# GRBL-Control.net
KiCad netlist of a schematic drawn in EAGLE
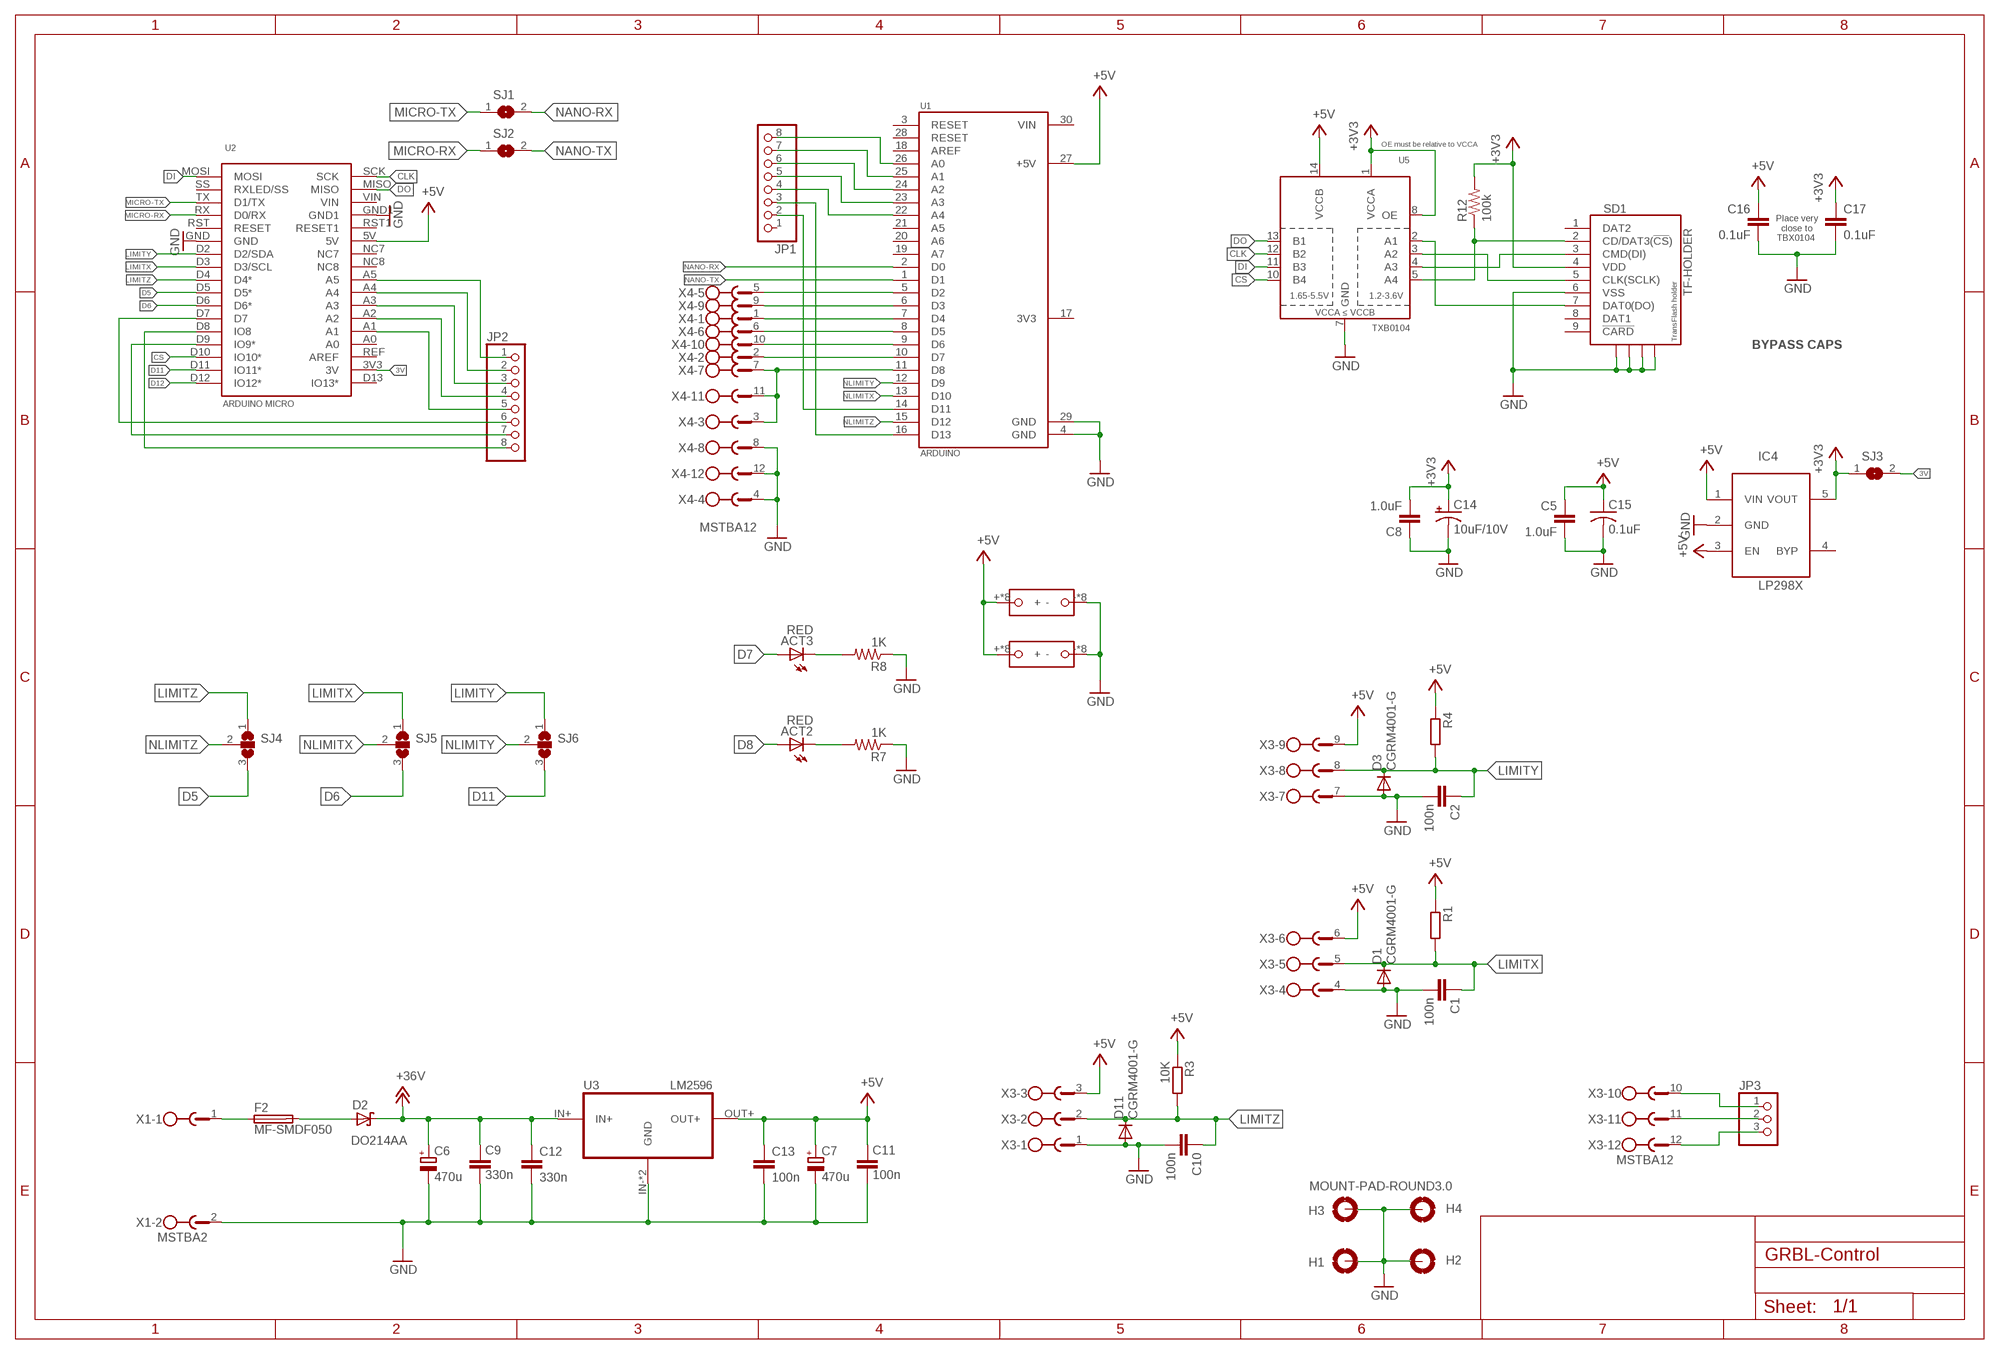
[diagram p0: schematic, sheet 1]

(export (version "E")
  (design (tool "Eeschema 10.0.6"))
  (components
    (comp (ref "ACT2")
      (value "RED")
      (footprint "eagle-import:CHIP-LED0805")
      (libsource (lib "eagle-import") (part "LEDCHIP-LED0805"))
    )
    (comp (ref "ACT3")
      (value "RED")
      (footprint "eagle-import:CHIP-LED0805")
      (libsource (lib "eagle-import") (part "LEDCHIP-LED0805"))
    )
    (comp (ref "C1")
      (value "100n")
      (footprint "eagle-import:C0603")
      (libsource (lib "eagle-import") (part "C-EUC0603"))
    )
    (comp (ref "C2")
      (value "100n")
      (footprint "eagle-import:C0603")
      (libsource (lib "eagle-import") (part "C-EUC0603"))
    )
    (comp (ref "C5")
      (value "1.0uF")
      (footprint "eagle-import:0603-CAP")
      (libsource (lib "eagle-import") (part "1.0UF-16V-10%(0603)"))
    )
    (comp (ref "C6")
      (value "470u")
      (footprint "eagle-import:E3,5-8")
      (libsource (lib "eagle-import") (part "CPOL-EUE3.5-8"))
    )
    (comp (ref "C7")
      (value "470u")
      (footprint "eagle-import:E3,5-8")
      (libsource (lib "eagle-import") (part "CPOL-EUE3.5-8"))
    )
    (comp (ref "C8")
      (value "1.0uF")
      (footprint "eagle-import:0603-CAP")
      (libsource (lib "eagle-import") (part "1.0UF-16V-10%(0603)"))
    )
    (comp (ref "C9")
      (value "330n")
      (footprint "eagle-import:C0603")
      (libsource (lib "eagle-import") (part "C-EUC0603"))
    )
    (comp (ref "C10")
      (value "100n")
      (footprint "eagle-import:C0603")
      (libsource (lib "eagle-import") (part "C-EUC0603"))
    )
    (comp (ref "C11")
      (value "100n")
      (footprint "eagle-import:C0603")
      (libsource (lib "eagle-import") (part "C-EUC0603"))
    )
    (comp (ref "C12")
      (value "330n")
      (footprint "eagle-import:C050-025X075")
      (libsource (lib "eagle-import") (part "RavinLib_C-EU050-025X075"))
    )
    (comp (ref "C13")
      (value "100n")
      (footprint "eagle-import:C050-025X075")
      (libsource (lib "eagle-import") (part "RavinLib_C-EU050-025X075"))
    )
    (comp (ref "C14")
      (value "10uF/10V")
      (footprint "eagle-import:A_3216-18R")
      (libsource (lib "eagle-import") (part "CPOL-USA/3216-18R"))
    )
    (comp (ref "C15")
      (value "0.1uF")
      (footprint "eagle-import:C0805K")
      (libsource (lib "eagle-import") (part "C-USC0805K"))
    )
    (comp (ref "C16")
      (value "0.1uF")
      (footprint "eagle-import:0603-CAP")
      (libsource (lib "eagle-import") (part "0.1UF-25V(+80/-20%)(0603)"))
    )
    (comp (ref "C17")
      (value "0.1uF")
      (footprint "eagle-import:0603-CAP")
      (libsource (lib "eagle-import") (part "0.1UF-25V(+80/-20%)(0603)"))
    )
    (comp (ref "D1")
      (value "CGRM4001-G")
      (footprint "eagle-import:SOD-123_MINI-SMA")
      (libsource (lib "eagle-import") (part "CGRM400-G1"))
    )
    (comp (ref "D2")
      (value "DO214AA")
      (footprint "eagle-import:SMB")
      (fields (field (name "PART-NO") "DO214AA"))
      (libsource (lib "eagle-import") (part "MBRS130LT3"))
    )
    (comp (ref "D3")
      (value "CGRM4001-G")
      (footprint "eagle-import:SOD-123_MINI-SMA")
      (libsource (lib "eagle-import") (part "CGRM400-G1"))
    )
    (comp (ref "D11")
      (value "CGRM4001-G")
      (footprint "eagle-import:SOD-123_MINI-SMA")
      (libsource (lib "eagle-import") (part "CGRM400-G1"))
    )
    (comp (ref "F2")
      (value "MF-SMDF050")
      (footprint "eagle-import:MF-SMDF050")
      (libsource (lib "eagle-import") (part "MF-SMDF050"))
    )
    (comp (ref "H1")
      (value "MOUNT-PAD-ROUND3.0")
      (footprint "eagle-import:3,0-PAD")
      (libsource (lib "eagle-import") (part "MOUNT-PAD-ROUND3.0"))
    )
    (comp (ref "H2")
      (value "MOUNT-PAD-ROUND3.0")
      (footprint "eagle-import:3,0-PAD")
      (libsource (lib "eagle-import") (part "MOUNT-PAD-ROUND3.0"))
    )
    (comp (ref "H3")
      (value "MOUNT-PAD-ROUND3.0")
      (footprint "eagle-import:3,0-PAD")
      (libsource (lib "eagle-import") (part "MOUNT-PAD-ROUND3.0"))
    )
    (comp (ref "H4")
      (value "MOUNT-PAD-ROUND3.0")
      (footprint "eagle-import:3,0-PAD")
      (libsource (lib "eagle-import") (part "MOUNT-PAD-ROUND3.0"))
    )
    (comp (ref "IC4")
      (value "LP298XS")
      (footprint "eagle-import:SOT23-5L")
      (libsource (lib "eagle-import") (part "LP298XS"))
    )
    (comp (ref "JP1")
      (value "PINHD-1X8BIG")
      (footprint "eagle-import:1X08-BIG")
      (libsource (lib "eagle-import") (part "PINHD-1X8BIG"))
    )
    (comp (ref "JP2")
      (value "PINHD-1X8BIG")
      (footprint "eagle-import:1X08-BIG")
      (libsource (lib "eagle-import") (part "PINHD-1X8BIG"))
    )
    (comp (ref "JP3")
      (value "PINHD-1X3")
      (footprint "eagle-import:1X03")
      (libsource (lib "eagle-import") (part "PINHD-1X3"))
    )
    (comp (ref "R1")
      (value "R-EU_R0603")
      (footprint "eagle-import:R0603")
      (libsource (lib "eagle-import") (part "R-EU_R0603"))
    )
    (comp (ref "R3")
      (value "10K")
      (footprint "eagle-import:R0603")
      (libsource (lib "eagle-import") (part "R-EU_R0603"))
    )
    (comp (ref "R4")
      (value "R-EU_R0603")
      (footprint "eagle-import:R0603")
      (libsource (lib "eagle-import") (part "R-EU_R0603"))
    )
    (comp (ref "R7")
      (value "1K")
      (footprint "eagle-import:R0805")
      (libsource (lib "eagle-import") (part "R-US_R0805"))
    )
    (comp (ref "R8")
      (value "1K")
      (footprint "eagle-import:R0805")
      (libsource (lib "eagle-import") (part "R-US_R0805"))
    )
    (comp (ref "R12")
      (value "100k")
      (footprint "eagle-import:0603-RES")
      (libsource (lib "eagle-import") (part "100KOHM-1/10W-1%(0603)"))
    )
    (comp (ref "SD1")
      (value "TF-HOLDER")
      (footprint "eagle-import:TF-PULL")
      (libsource (lib "eagle-import") (part "TF-HOLDER"))
    )
    (comp (ref "SJ1") (value "SJ") (footprint "eagle-import:SJ") (libsource (lib "eagle-import") (part "SJ")))
    (comp (ref "SJ2") (value "SJ") (footprint "eagle-import:SJ") (libsource (lib "eagle-import") (part "SJ")))
    (comp (ref "SJ3") (value "SJ") (footprint "eagle-import:SJ") (libsource (lib "eagle-import") (part "SJ")))
    (comp (ref "SJ4")
      (value "SJ2W")
      (footprint "eagle-import:SJ_2")
      (libsource (lib "eagle-import") (part "SJ2W"))
    )
    (comp (ref "SJ5")
      (value "SJ2W")
      (footprint "eagle-import:SJ_2")
      (libsource (lib "eagle-import") (part "SJ2W"))
    )
    (comp (ref "SJ6")
      (value "SJ2W")
      (footprint "eagle-import:SJ_2")
      (libsource (lib "eagle-import") (part "SJ2W"))
    )
    (comp (ref "U$1")
      (value "DEV_GRID")
      (footprint "eagle-import:DEV_GRID")
      (libsource (lib "eagle-import") (part "DEV_GRID"))
    )
    (comp (ref "U$2")
      (value "DEV_GRID")
      (footprint "eagle-import:DEV_GRID")
      (libsource (lib "eagle-import") (part "DEV_GRID"))
    )
    (comp (ref "U1")
      (value "ARDUINO")
      (footprint "eagle-import:ARDUINO_A000005")
      (libsource (lib "eagle-import") (part "ARDUINO"))
    )
    (comp (ref "U2")
      (value "ARDUINO MICRO")
      (footprint "eagle-import:ARDUINO-MICRO")
      (libsource (lib "eagle-import") (part "ARDUINO_MICROFOOTPRINT"))
    )
    (comp (ref "U3")
      (value "LM2596")
      (footprint "eagle-import:BUCK-LM2596")
      (libsource (lib "eagle-import") (part "LM2596-DCDC"))
    )
    (comp (ref "U5")
      (value "TXB0104")
      (footprint "eagle-import:SO14")
      (libsource (lib "eagle-import") (part "TXB0104PWRSOIC14"))
    )
    (comp (ref "X1")
      (value "MSTBA2")
      (footprint "eagle-import:MSTBA2")
      (fields (field (name "MF") "FARNELL") (field (name "MPN") "1757242"))
      (libsource (lib "eagle-import") (part "MSTBA2"))
    )
    (comp (ref "X3")
      (value "MSTBA12")
      (footprint "eagle-import:MSTBA12")
      (fields (field (name "MPN") "1757349"))
      (libsource (lib "eagle-import") (part "MSTBA12"))
    )
    (comp (ref "X4")
      (value "MSTBA12")
      (footprint "eagle-import:MSTBA12")
      (fields (field (name "MPN") "1757349"))
      (libsource (lib "eagle-import") (part "MSTBA12"))
    )
  )
  (nets
    (net (code "1") (name "+3V3") (class "Default")
      (node (ref "C14") (pin "+") (pinfunction "+_+") (pintype "passive"))
      (node (ref "C17") (pin "1") (pinfunction "1_1") (pintype "passive"))
      (node (ref "C8") (pin "2") (pinfunction "2_2") (pintype "passive"))
      (node (ref "IC4") (pin "5") (pinfunction "VOUT_5") (pintype "bidirectional"))
      (node (ref "R12") (pin "2") (pinfunction "2_2") (pintype "passive"))
      (node (ref "SD1") (pin "4") (pinfunction "VDD_4") (pintype "power_in"))
      (node (ref "SJ3") (pin "1") (pinfunction "1_1") (pintype "passive"))
      (node (ref "U5") (pin "1") (pinfunction "VCCA_1") (pintype "bidirectional"))
      (node (ref "U5") (pin "8") (pinfunction "OE_8") (pintype "bidirectional"))
    )
    (net (code "2") (name "+5V") (class "Default")
      (node (ref "C11") (pin "1") (pinfunction "1_1") (pintype "passive"))
      (node (ref "C13") (pin "1") (pinfunction "1_1") (pintype "passive"))
      (node (ref "C15") (pin "1") (pinfunction "1_1") (pintype "passive"))
      (node (ref "C16") (pin "1") (pinfunction "1_1") (pintype "passive"))
      (node (ref "C5") (pin "1") (pinfunction "1_1") (pintype "passive"))
      (node (ref "C7") (pin "+") (pinfunction "+_+") (pintype "passive"))
      (node (ref "IC4") (pin "1") (pinfunction "VIN_1") (pintype "bidirectional"))
      (node (ref "IC4") (pin "3") (pinfunction "EN_3") (pintype "bidirectional"))
      (node (ref "R1") (pin "1") (pinfunction "1_1") (pintype "passive"))
      (node (ref "R3") (pin "1") (pinfunction "1_1") (pintype "passive"))
      (node (ref "R4") (pin "1") (pinfunction "1_1") (pintype "passive"))
      (node (ref "U$1") (pin "+") (pinfunction "+_+") (pintype "bidirectional"))
      (node (ref "U$1") (pin "P$49") (pinfunction "+_P$49") (pintype "bidirectional"))
      (node (ref "U$1") (pin "P$50") (pinfunction "+_P$50") (pintype "bidirectional"))
      (node (ref "U$1") (pin "P$51") (pinfunction "+_P$51") (pintype "bidirectional"))
      (node (ref "U$1") (pin "P$52") (pinfunction "+_P$52") (pintype "bidirectional"))
      (node (ref "U$1") (pin "P$53") (pinfunction "+_P$53") (pintype "bidirectional"))
      (node (ref "U$1") (pin "P$54") (pinfunction "+_P$54") (pintype "bidirectional"))
      (node (ref "U$1") (pin "P$55") (pinfunction "+_P$55") (pintype "bidirectional"))
      (node (ref "U$2") (pin "+") (pinfunction "+_+") (pintype "bidirectional"))
      (node (ref "U$2") (pin "P$49") (pinfunction "+_P$49") (pintype "bidirectional"))
      (node (ref "U$2") (pin "P$50") (pinfunction "+_P$50") (pintype "bidirectional"))
      (node (ref "U$2") (pin "P$51") (pinfunction "+_P$51") (pintype "bidirectional"))
      (node (ref "U$2") (pin "P$52") (pinfunction "+_P$52") (pintype "bidirectional"))
      (node (ref "U$2") (pin "P$53") (pinfunction "+_P$53") (pintype "bidirectional"))
      (node (ref "U$2") (pin "P$54") (pinfunction "+_P$54") (pintype "bidirectional"))
      (node (ref "U$2") (pin "P$55") (pinfunction "+_P$55") (pintype "bidirectional"))
      (node (ref "U1") (pin "27") (pinfunction "+5V_27") (pintype "power_in"))
      (node (ref "U2") (pin "5V") (pinfunction "5V_5V") (pintype "bidirectional"))
      (node (ref "U3") (pin "OUT+") (pinfunction "OUT+_OUT+") (pintype "bidirectional"))
      (node (ref "U5") (pin "14") (pinfunction "VCCB_14") (pintype "bidirectional"))
      (node (ref "X3") (pin "3") (pinfunction "1_3") (pintype "passive"))
      (node (ref "X3") (pin "6") (pinfunction "1_6") (pintype "passive"))
      (node (ref "X3") (pin "9") (pinfunction "1_9") (pintype "passive"))
    )
    (net (code "3") (name "+36V") (class "Default")
      (node (ref "C12") (pin "1") (pinfunction "1_1") (pintype "passive"))
      (node (ref "C6") (pin "+") (pinfunction "+_+") (pintype "passive"))
      (node (ref "C9") (pin "1") (pinfunction "1_1") (pintype "passive"))
      (node (ref "D2") (pin "C") (pinfunction "C_C") (pintype "passive"))
      (node (ref "U3") (pin "IN+") (pinfunction "IN+_IN+") (pintype "bidirectional"))
    )
    (net (code "4") (name "/VIN") (class "Default")
      (node (ref "U1") (pin "30") (pinfunction "VIN_30") (pintype "power_in"))
    )
    (net (code "5") (name "3V") (class "Default")
      (node (ref "SJ3") (pin "2") (pinfunction "2_2") (pintype "passive"))
      (node (ref "U2") (pin "3V3") (pinfunction "3V_3V3") (pintype "bidirectional"))
    )
    (net (code "6") (name "CLK") (class "Default")
      (node (ref "U2") (pin "SCK") (pinfunction "SCK_SCK") (pintype "bidirectional"))
      (node (ref "U5") (pin "12") (pinfunction "B2_12") (pintype "bidirectional"))
    )
    (net (code "7") (name "CS") (class "Default")
      (node (ref "U2") (pin "D10") (pinfunction "IO10*_D10") (pintype "bidirectional"))
      (node (ref "U5") (pin "10") (pinfunction "B4_10") (pintype "bidirectional"))
    )
    (net (code "8") (name "D5") (class "Default")
      (node (ref "SJ4") (pin "3") (pinfunction "3_3") (pintype "passive"))
      (node (ref "U2") (pin "D5") (pinfunction "D5*_D5") (pintype "bidirectional"))
    )
    (net (code "9") (name "D6") (class "Default")
      (node (ref "SJ5") (pin "3") (pinfunction "3_3") (pintype "passive"))
      (node (ref "U2") (pin "D6") (pinfunction "D6*_D6") (pintype "bidirectional"))
    )
    (net (code "10") (name "D7") (class "Default")
      (node (ref "ACT3") (pin "A") (pinfunction "A_A") (pintype "passive"))
      (node (ref "JP2") (pin "6") (pinfunction "6_6") (pintype "passive"))
      (node (ref "U2") (pin "D7") (pinfunction "D7_D7") (pintype "bidirectional"))
    )
    (net (code "11") (name "D8") (class "Default")
      (node (ref "ACT2") (pin "A") (pinfunction "A_A") (pintype "passive"))
      (node (ref "JP2") (pin "8") (pinfunction "8_8") (pintype "passive"))
      (node (ref "U2") (pin "D8") (pinfunction "IO8_D8") (pintype "bidirectional"))
    )
    (net (code "12") (name "D11") (class "Default")
      (node (ref "SJ6") (pin "3") (pinfunction "3_3") (pintype "passive"))
      (node (ref "U2") (pin "D11") (pinfunction "IO11*_D11") (pintype "bidirectional"))
    )
    (net (code "13") (name "D12") (class "Default")
      (node (ref "U2") (pin "D12") (pinfunction "IO12*_D12") (pintype "bidirectional"))
    )
    (net (code "14") (name "DI") (class "Default")
      (node (ref "U2") (pin "MOSI") (pinfunction "MOSI_MOSI") (pintype "bidirectional"))
      (node (ref "U5") (pin "11") (pinfunction "B3_11") (pintype "bidirectional"))
    )
    (net (code "15") (name "DO") (class "Default")
      (node (ref "U2") (pin "MISO") (pinfunction "MISO_MISO") (pintype "bidirectional"))
      (node (ref "U5") (pin "13") (pinfunction "B1_13") (pintype "bidirectional"))
    )
    (net (code "16") (name "GND") (class "Default")
      (node (ref "C1") (pin "2") (pinfunction "2_2") (pintype "passive"))
      (node (ref "C10") (pin "2") (pinfunction "2_2") (pintype "passive"))
      (node (ref "C11") (pin "2") (pinfunction "2_2") (pintype "passive"))
      (node (ref "C12") (pin "2") (pinfunction "2_2") (pintype "passive"))
      (node (ref "C13") (pin "2") (pinfunction "2_2") (pintype "passive"))
      (node (ref "C14") (pin "-") (pinfunction "-_-") (pintype "passive"))
      (node (ref "C15") (pin "2") (pinfunction "2_2") (pintype "passive"))
      (node (ref "C16") (pin "2") (pinfunction "2_2") (pintype "passive"))
      (node (ref "C17") (pin "2") (pinfunction "2_2") (pintype "passive"))
      (node (ref "C2") (pin "2") (pinfunction "2_2") (pintype "passive"))
      (node (ref "C5") (pin "2") (pinfunction "2_2") (pintype "passive"))
      (node (ref "C6") (pin "-") (pinfunction "-_-") (pintype "passive"))
      (node (ref "C7") (pin "-") (pinfunction "-_-") (pintype "passive"))
      (node (ref "C8") (pin "1") (pinfunction "1_1") (pintype "passive"))
      (node (ref "C9") (pin "2") (pinfunction "2_2") (pintype "passive"))
      (node (ref "D1") (pin "A") (pinfunction "A_A") (pintype "passive"))
      (node (ref "D11") (pin "A") (pinfunction "A_A") (pintype "passive"))
      (node (ref "D3") (pin "A") (pinfunction "A_A") (pintype "passive"))
      (node (ref "H1") (pin "B3,0") (pinfunction "MOUNT_B3,0") (pintype "passive"))
      (node (ref "H1") (pin "P$1") (pinfunction "MOUNT_P$1") (pintype "passive"))
      (node (ref "H1") (pin "P$2") (pinfunction "MOUNT_P$2") (pintype "passive"))
      (node (ref "H1") (pin "P$3") (pinfunction "MOUNT_P$3") (pintype "passive"))
      (node (ref "H1") (pin "P$4") (pinfunction "MOUNT_P$4") (pintype "passive"))
      (node (ref "H1") (pin "P$5") (pinfunction "MOUNT_P$5") (pintype "passive"))
      (node (ref "H1") (pin "P$6") (pinfunction "MOUNT_P$6") (pintype "passive"))
      (node (ref "H1") (pin "P$7") (pinfunction "MOUNT_P$7") (pintype "passive"))
      (node (ref "H1") (pin "P$8") (pinfunction "MOUNT_P$8") (pintype "passive"))
      (node (ref "H2") (pin "B3,0") (pinfunction "MOUNT_B3,0") (pintype "passive"))
      (node (ref "H2") (pin "P$1") (pinfunction "MOUNT_P$1") (pintype "passive"))
      (node (ref "H2") (pin "P$2") (pinfunction "MOUNT_P$2") (pintype "passive"))
      (node (ref "H2") (pin "P$3") (pinfunction "MOUNT_P$3") (pintype "passive"))
      (node (ref "H2") (pin "P$4") (pinfunction "MOUNT_P$4") (pintype "passive"))
      (node (ref "H2") (pin "P$5") (pinfunction "MOUNT_P$5") (pintype "passive"))
      (node (ref "H2") (pin "P$6") (pinfunction "MOUNT_P$6") (pintype "passive"))
      (node (ref "H2") (pin "P$7") (pinfunction "MOUNT_P$7") (pintype "passive"))
      (node (ref "H2") (pin "P$8") (pinfunction "MOUNT_P$8") (pintype "passive"))
      (node (ref "H3") (pin "B3,0") (pinfunction "MOUNT_B3,0") (pintype "passive"))
      (node (ref "H3") (pin "P$1") (pinfunction "MOUNT_P$1") (pintype "passive"))
      (node (ref "H3") (pin "P$2") (pinfunction "MOUNT_P$2") (pintype "passive"))
      (node (ref "H3") (pin "P$3") (pinfunction "MOUNT_P$3") (pintype "passive"))
      (node (ref "H3") (pin "P$4") (pinfunction "MOUNT_P$4") (pintype "passive"))
      (node (ref "H3") (pin "P$5") (pinfunction "MOUNT_P$5") (pintype "passive"))
      (node (ref "H3") (pin "P$6") (pinfunction "MOUNT_P$6") (pintype "passive"))
      (node (ref "H3") (pin "P$7") (pinfunction "MOUNT_P$7") (pintype "passive"))
      (node (ref "H3") (pin "P$8") (pinfunction "MOUNT_P$8") (pintype "passive"))
      (node (ref "H4") (pin "B3,0") (pinfunction "MOUNT_B3,0") (pintype "passive"))
      (node (ref "H4") (pin "P$1") (pinfunction "MOUNT_P$1") (pintype "passive"))
      (node (ref "H4") (pin "P$2") (pinfunction "MOUNT_P$2") (pintype "passive"))
      (node (ref "H4") (pin "P$3") (pinfunction "MOUNT_P$3") (pintype "passive"))
      (node (ref "H4") (pin "P$4") (pinfunction "MOUNT_P$4") (pintype "passive"))
      (node (ref "H4") (pin "P$5") (pinfunction "MOUNT_P$5") (pintype "passive"))
      (node (ref "H4") (pin "P$6") (pinfunction "MOUNT_P$6") (pintype "passive"))
      (node (ref "H4") (pin "P$7") (pinfunction "MOUNT_P$7") (pintype "passive"))
      (node (ref "H4") (pin "P$8") (pinfunction "MOUNT_P$8") (pintype "passive"))
      (node (ref "IC4") (pin "2") (pinfunction "GND_2") (pintype "bidirectional"))
      (node (ref "R7") (pin "1") (pinfunction "1_1") (pintype "passive"))
      (node (ref "R8") (pin "1") (pinfunction "1_1") (pintype "passive"))
      (node (ref "SD1") (pin "6") (pinfunction "VSS_6") (pintype "power_in"))
      (node (ref "SD1") (pin "S1") (pinfunction "S1_S1") (pintype "passive"))
      (node (ref "SD1") (pin "S2") (pinfunction "S2_S2") (pintype "passive"))
      (node (ref "SD1") (pin "S3") (pinfunction "S3_S3") (pintype "passive"))
      (node (ref "SD1") (pin "S4") (pinfunction "S4_S4") (pintype "passive"))
      (node (ref "U$1") (pin "-") (pinfunction "-_-") (pintype "bidirectional"))
      (node (ref "U$1") (pin "P$57") (pinfunction "-_P$57") (pintype "bidirectional"))
      (node (ref "U$1") (pin "P$58") (pinfunction "-_P$58") (pintype "bidirectional"))
      (node (ref "U$1") (pin "P$59") (pinfunction "-_P$59") (pintype "bidirectional"))
      (node (ref "U$1") (pin "P$60") (pinfunction "-_P$60") (pintype "bidirectional"))
      (node (ref "U$1") (pin "P$61") (pinfunction "-_P$61") (pintype "bidirectional"))
      (node (ref "U$1") (pin "P$62") (pinfunction "-_P$62") (pintype "bidirectional"))
      (node (ref "U$1") (pin "P$63") (pinfunction "-_P$63") (pintype "bidirectional"))
      (node (ref "U$2") (pin "-") (pinfunction "-_-") (pintype "bidirectional"))
      (node (ref "U$2") (pin "P$57") (pinfunction "-_P$57") (pintype "bidirectional"))
      (node (ref "U$2") (pin "P$58") (pinfunction "-_P$58") (pintype "bidirectional"))
      (node (ref "U$2") (pin "P$59") (pinfunction "-_P$59") (pintype "bidirectional"))
      (node (ref "U$2") (pin "P$60") (pinfunction "-_P$60") (pintype "bidirectional"))
      (node (ref "U$2") (pin "P$61") (pinfunction "-_P$61") (pintype "bidirectional"))
      (node (ref "U$2") (pin "P$62") (pinfunction "-_P$62") (pintype "bidirectional"))
      (node (ref "U$2") (pin "P$63") (pinfunction "-_P$63") (pintype "bidirectional"))
      (node (ref "U1") (pin "29") (pinfunction "GND_29") (pintype "power_in"))
      (node (ref "U1") (pin "4") (pinfunction "GND_4") (pintype "power_in"))
      (node (ref "U2") (pin "GND") (pinfunction "GND_GND") (pintype "bidirectional"))
      (node (ref "U2") (pin "GND1") (pinfunction "GND1_GND1") (pintype "bidirectional"))
      (node (ref "U3") (pin "IN-") (pinfunction "GND_IN-") (pintype "bidirectional"))
      (node (ref "U3") (pin "OUT-") (pinfunction "GND_OUT-") (pintype "bidirectional"))
      (node (ref "U5") (pin "7") (pinfunction "GND_7") (pintype "bidirectional"))
      (node (ref "X1") (pin "2") (pinfunction "1_2") (pintype "passive"))
      (node (ref "X3") (pin "1") (pinfunction "1_1") (pintype "passive"))
      (node (ref "X3") (pin "4") (pinfunction "1_4") (pintype "passive"))
      (node (ref "X3") (pin "7") (pinfunction "1_7") (pintype "passive"))
      (node (ref "X4") (pin "12") (pinfunction "1_12") (pintype "passive"))
      (node (ref "X4") (pin "4") (pinfunction "1_4") (pintype "passive"))
      (node (ref "X4") (pin "8") (pinfunction "1_8") (pintype "passive"))
    )
    (net (code "17") (name "LIMITX") (class "Default")
      (node (ref "C1") (pin "1") (pinfunction "1_1") (pintype "passive"))
      (node (ref "D1") (pin "C") (pinfunction "C_C") (pintype "passive"))
      (node (ref "R1") (pin "2") (pinfunction "2_2") (pintype "passive"))
      (node (ref "SJ5") (pin "1") (pinfunction "1_1") (pintype "passive"))
      (node (ref "U2") (pin "D3") (pinfunction "D3/SCL_D3") (pintype "bidirectional"))
      (node (ref "X3") (pin "5") (pinfunction "1_5") (pintype "passive"))
    )
    (net (code "18") (name "LIMITY") (class "Default")
      (node (ref "C2") (pin "1") (pinfunction "1_1") (pintype "passive"))
      (node (ref "D3") (pin "C") (pinfunction "C_C") (pintype "passive"))
      (node (ref "R4") (pin "2") (pinfunction "2_2") (pintype "passive"))
      (node (ref "SJ6") (pin "1") (pinfunction "1_1") (pintype "passive"))
      (node (ref "U2") (pin "D2") (pinfunction "D2/SDA_D2") (pintype "bidirectional"))
      (node (ref "X3") (pin "8") (pinfunction "1_8") (pintype "passive"))
    )
    (net (code "19") (name "LIMITZ") (class "Default")
      (node (ref "C10") (pin "1") (pinfunction "1_1") (pintype "passive"))
      (node (ref "D11") (pin "C") (pinfunction "C_C") (pintype "passive"))
      (node (ref "R3") (pin "2") (pinfunction "2_2") (pintype "passive"))
      (node (ref "SJ4") (pin "1") (pinfunction "1_1") (pintype "passive"))
      (node (ref "U2") (pin "D4") (pinfunction "D4*_D4") (pintype "bidirectional"))
      (node (ref "X3") (pin "2") (pinfunction "1_2") (pintype "passive"))
    )
    (net (code "20") (name "MICRO-RX") (class "Default")
      (node (ref "SJ2") (pin "1") (pinfunction "1_1") (pintype "passive"))
      (node (ref "U2") (pin "RX") (pinfunction "D0/RX_RX") (pintype "bidirectional"))
    )
    (net (code "21") (name "MICRO-TX") (class "Default")
      (node (ref "SJ1") (pin "1") (pinfunction "1_1") (pintype "passive"))
      (node (ref "U2") (pin "TX") (pinfunction "D1/TX_TX") (pintype "bidirectional"))
    )
    (net (code "22") (name "NANO-RX") (class "Default")
      (node (ref "SJ1") (pin "2") (pinfunction "2_2") (pintype "passive"))
      (node (ref "U1") (pin "2") (pinfunction "D0_2") (pintype "bidirectional"))
    )
    (net (code "23") (name "NANO-TX") (class "Default")
      (node (ref "SJ2") (pin "2") (pinfunction "2_2") (pintype "passive"))
      (node (ref "U1") (pin "1") (pinfunction "D1_1") (pintype "bidirectional"))
    )
    (net (code "24") (name "NLIMITX") (class "Default")
      (node (ref "SJ5") (pin "2") (pinfunction "2_2") (pintype "passive"))
      (node (ref "U1") (pin "13") (pinfunction "D10_13") (pintype "bidirectional"))
    )
    (net (code "25") (name "NLIMITY") (class "Default")
      (node (ref "SJ6") (pin "2") (pinfunction "2_2") (pintype "passive"))
      (node (ref "U1") (pin "12") (pinfunction "D9_12") (pintype "bidirectional"))
    )
    (net (code "26") (name "NLIMITZ") (class "Default")
      (node (ref "SJ4") (pin "2") (pinfunction "2_2") (pintype "passive"))
      (node (ref "U1") (pin "15") (pinfunction "D12_15") (pintype "bidirectional"))
    )
    (net (code "27") (name "Net-(ACT2-PadC)") (class "Default")
      (node (ref "ACT2") (pin "C") (pinfunction "C_C") (pintype "passive"))
      (node (ref "R7") (pin "2") (pinfunction "2_2") (pintype "passive"))
    )
    (net (code "28") (name "Net-(ACT3-PadC)") (class "Default")
      (node (ref "ACT3") (pin "C") (pinfunction "C_C") (pintype "passive"))
      (node (ref "R8") (pin "2") (pinfunction "2_2") (pintype "passive"))
    )
    (net (code "29") (name "Net-(D2-PadA)") (class "Default")
      (node (ref "D2") (pin "A") (pinfunction "A_A") (pintype "passive"))
      (node (ref "F2") (pin "2") (pinfunction "2_2") (pintype "passive"))
    )
    (net (code "30") (name "Net-(F2-Pad1)") (class "Default")
      (node (ref "F2") (pin "1") (pinfunction "1_1") (pintype "passive"))
      (node (ref "X1") (pin "1") (pinfunction "1_1") (pintype "passive"))
    )
    (net (code "31") (name "Net-(JP2-Pad1)") (class "Default")
      (node (ref "JP2") (pin "1") (pinfunction "1_1") (pintype "passive"))
      (node (ref "U2") (pin "A5") (pinfunction "A5_A5") (pintype "bidirectional"))
    )
    (net (code "32") (name "Net-(JP2-Pad2)") (class "Default")
      (node (ref "JP2") (pin "2") (pinfunction "2_2") (pintype "passive"))
      (node (ref "U2") (pin "A4") (pinfunction "A4_A4") (pintype "bidirectional"))
    )
    (net (code "33") (name "Net-(JP2-Pad3)") (class "Default")
      (node (ref "JP2") (pin "3") (pinfunction "3_3") (pintype "passive"))
      (node (ref "U2") (pin "A3") (pinfunction "A3_A3") (pintype "bidirectional"))
    )
    (net (code "34") (name "Net-(JP2-Pad4)") (class "Default")
      (node (ref "JP2") (pin "4") (pinfunction "4_4") (pintype "passive"))
      (node (ref "U2") (pin "A2") (pinfunction "A2_A2") (pintype "bidirectional"))
    )
    (net (code "35") (name "Net-(JP2-Pad5)") (class "Default")
      (node (ref "JP2") (pin "5") (pinfunction "5_5") (pintype "passive"))
      (node (ref "U2") (pin "A1") (pinfunction "A1_A1") (pintype "bidirectional"))
    )
    (net (code "36") (name "Net-(SD1-CD{slash}DAT3(~{CS}))") (class "Default")
      (node (ref "R12") (pin "1") (pinfunction "1_1") (pintype "passive"))
      (node (ref "SD1") (pin "2") (pinfunction "CD/DAT3(~{CS})_2") (pintype "bidirectional"))
      (node (ref "U5") (pin "5") (pinfunction "A4_5") (pintype "bidirectional"))
    )
    (net (code "37") (name "Net-(SD1-CLK(SCLK))") (class "Default")
      (node (ref "SD1") (pin "5") (pinfunction "CLK(SCLK)_5") (pintype "input"))
      (node (ref "U5") (pin "3") (pinfunction "A2_3") (pintype "bidirectional"))
    )
    (net (code "38") (name "Net-(SD1-CMD(DI))") (class "Default")
      (node (ref "SD1") (pin "3") (pinfunction "CMD(DI)_3") (pintype "bidirectional"))
      (node (ref "U5") (pin "4") (pinfunction "A3_4") (pintype "bidirectional"))
    )
    (net (code "39") (name "Net-(SD1-DAT0(DO))") (class "Default")
      (node (ref "SD1") (pin "7") (pinfunction "DAT0(DO)_7") (pintype "bidirectional"))
      (node (ref "U5") (pin "2") (pinfunction "A1_2") (pintype "bidirectional"))
    )
    (net (code "40") (name "Net-(U1-A0)") (class "Default")
      (node (ref "JP1") (pin "8") (pinfunction "8_8") (pintype "passive"))
      (node (ref "U1") (pin "26") (pinfunction "A0_26") (pintype "input"))
    )
    (net (code "41") (name "Net-(U1-A1)") (class "Default")
      (node (ref "JP1") (pin "7") (pinfunction "7_7") (pintype "passive"))
      (node (ref "U1") (pin "25") (pinfunction "A1_25") (pintype "input"))
    )
    (net (code "42") (name "Net-(U1-A2)") (class "Default")
      (node (ref "JP1") (pin "6") (pinfunction "6_6") (pintype "passive"))
      (node (ref "U1") (pin "24") (pinfunction "A2_24") (pintype "input"))
    )
    (net (code "43") (name "Net-(U1-A3)") (class "Default")
      (node (ref "JP1") (pin "5") (pinfunction "5_5") (pintype "passive"))
      (node (ref "U1") (pin "23") (pinfunction "A3_23") (pintype "input"))
    )
    (net (code "44") (name "Net-(U1-A4)") (class "Default")
      (node (ref "JP1") (pin "4") (pinfunction "4_4") (pintype "passive"))
      (node (ref "U1") (pin "22") (pinfunction "A4_22") (pintype "input"))
    )
    (net (code "45") (name "Net-(U1-D2)") (class "Default")
      (node (ref "U1") (pin "5") (pinfunction "D2_5") (pintype "bidirectional"))
      (node (ref "X4") (pin "5") (pinfunction "1_5") (pintype "passive"))
    )
    (net (code "46") (name "Net-(U1-D3)") (class "Default")
      (node (ref "U1") (pin "6") (pinfunction "D3_6") (pintype "bidirectional"))
      (node (ref "X4") (pin "9") (pinfunction "1_9") (pintype "passive"))
    )
    (net (code "47") (name "Net-(U1-D4)") (class "Default")
      (node (ref "U1") (pin "7") (pinfunction "D4_7") (pintype "bidirectional"))
      (node (ref "X4") (pin "1") (pinfunction "1_1") (pintype "passive"))
    )
    (net (code "48") (name "Net-(U1-D5)") (class "Default")
      (node (ref "U1") (pin "8") (pinfunction "D5_8") (pintype "bidirectional"))
      (node (ref "X4") (pin "6") (pinfunction "1_6") (pintype "passive"))
    )
    (net (code "49") (name "Net-(U1-D6)") (class "Default")
      (node (ref "U1") (pin "9") (pinfunction "D6_9") (pintype "bidirectional"))
      (node (ref "X4") (pin "10") (pinfunction "1_10") (pintype "passive"))
    )
    (net (code "50") (name "Net-(U1-D7)") (class "Default")
      (node (ref "U1") (pin "10") (pinfunction "D7_10") (pintype "bidirectional"))
      (node (ref "X4") (pin "2") (pinfunction "1_2") (pintype "passive"))
    )
    (net (code "51") (name "Net-(U1-D8)") (class "Default")
      (node (ref "U1") (pin "11") (pinfunction "D8_11") (pintype "bidirectional"))
      (node (ref "X4") (pin "11") (pinfunction "1_11") (pintype "passive"))
      (node (ref "X4") (pin "3") (pinfunction "1_3") (pintype "passive"))
      (node (ref "X4") (pin "7") (pinfunction "1_7") (pintype "passive"))
    )
    (net (code "52") (name "Net-(U1-D11)") (class "Default")
      (node (ref "JP1") (pin "2") (pinfunction "2_2") (pintype "passive"))
      (node (ref "U1") (pin "14") (pinfunction "D11_14") (pintype "bidirectional"))
    )
    (net (code "53") (name "Net-(U1-D13)") (class "Default")
      (node (ref "JP1") (pin "3") (pinfunction "3_3") (pintype "passive"))
      (node (ref "U1") (pin "16") (pinfunction "D13_16") (pintype "bidirectional"))
    )
    (net (code "54") (name "Net-(U2-IO9*)") (class "Default")
      (node (ref "JP2") (pin "7") (pinfunction "7_7") (pintype "passive"))
      (node (ref "U2") (pin "D9") (pinfunction "IO9*_D9") (pintype "bidirectional"))
    )
    (net (code "55") (name "Net-(X3B-1)") (class "Default")
      (node (ref "JP3") (pin "1") (pinfunction "1_1") (pintype "passive"))
      (node (ref "X3") (pin "10") (pinfunction "1_10") (pintype "passive"))
    )
    (net (code "56") (name "Net-(X3C-1)") (class "Default")
      (node (ref "JP3") (pin "2") (pinfunction "2_2") (pintype "passive"))
      (node (ref "X3") (pin "11") (pinfunction "1_11") (pintype "passive"))
    )
    (net (code "57") (name "Net-(X3D-1)") (class "Default")
      (node (ref "JP3") (pin "3") (pinfunction "3_3") (pintype "passive"))
      (node (ref "X3") (pin "12") (pinfunction "1_12") (pintype "passive"))
    )
    (net (code "58") (name "unconnected-(IC4-BYP-Pad4)") (class "Default")
      (node (ref "IC4") (pin "4") (pinfunction "BYP_4") (pintype "bidirectional"))
    )
    (net (code "59") (name "unconnected-(JP1-Pad1)") (class "Default")
      (node (ref "JP1") (pin "1") (pinfunction "1_1") (pintype "passive"))
    )
    (net (code "60") (name "unconnected-(SD1-DAT1-Pad8)") (class "Default")
      (node (ref "SD1") (pin "8") (pinfunction "DAT1_8") (pintype "bidirectional"))
    )
    (net (code "61") (name "unconnected-(SD1-DAT2-Pad1)") (class "Default")
      (node (ref "SD1") (pin "1") (pinfunction "DAT2_1") (pintype "bidirectional"))
    )
    (net (code "62") (name "unconnected-(SD1-~{CARD}-Pad9)") (class "Default")
      (node (ref "SD1") (pin "9") (pinfunction "~{CARD}_9") (pintype "passive"))
    )
    (net (code "63") (name "unconnected-(U1-3V3-Pad17)") (class "Default")
      (node (ref "U1") (pin "17") (pinfunction "3V3_17") (pintype "output"))
    )
    (net (code "64") (name "unconnected-(U1-A5-Pad21)") (class "Default")
      (node (ref "U1") (pin "21") (pinfunction "A5_21") (pintype "input"))
    )
    (net (code "65") (name "unconnected-(U1-A6-Pad20)") (class "Default")
      (node (ref "U1") (pin "20") (pinfunction "A6_20") (pintype "input"))
    )
    (net (code "66") (name "unconnected-(U1-A7-Pad19)") (class "Default")
      (node (ref "U1") (pin "19") (pinfunction "A7_19") (pintype "input"))
    )
    (net (code "67") (name "unconnected-(U1-AREF-Pad18)") (class "Default")
      (node (ref "U1") (pin "18") (pinfunction "AREF_18") (pintype "input"))
    )
    (net (code "68") (name "unconnected-(U1-RESET-Pad3)") (class "Default")
      (node (ref "U1") (pin "3") (pinfunction "RESET_3") (pintype "input"))
    )
    (net (code "69") (name "unconnected-(U1-RESET-Pad28)") (class "Default")
      (node (ref "U1") (pin "28") (pinfunction "RESET_28") (pintype "input"))
    )
    (net (code "70") (name "unconnected-(U2-AREF-PadREF)") (class "Default")
      (node (ref "U2") (pin "REF") (pinfunction "AREF_REF") (pintype "bidirectional"))
    )
    (net (code "71") (name "unconnected-(U2-IO13*-PadD13)") (class "Default")
      (node (ref "U2") (pin "D13") (pinfunction "IO13*_D13") (pintype "bidirectional"))
    )
    (net (code "72") (name "unconnected-(U2-PadA0)") (class "Default")
      (node (ref "U2") (pin "A0") (pinfunction "A0_A0") (pintype "bidirectional"))
    )
    (net (code "73") (name "unconnected-(U2-PadNC7)") (class "Default")
      (node (ref "U2") (pin "NC7") (pinfunction "NC7_NC7") (pintype "bidirectional"))
    )
    (net (code "74") (name "unconnected-(U2-PadNC8)") (class "Default")
      (node (ref "U2") (pin "NC8") (pinfunction "NC8_NC8") (pintype "bidirectional"))
    )
    (net (code "75") (name "unconnected-(U2-PadVIN)") (class "Default")
      (node (ref "U2") (pin "VIN") (pinfunction "VIN_VIN") (pintype "bidirectional"))
    )
    (net (code "76") (name "unconnected-(U2-RESET-PadRST)") (class "Default")
      (node (ref "U2") (pin "RST") (pinfunction "RESET_RST") (pintype "bidirectional"))
    )
    (net (code "77") (name "unconnected-(U2-RESET1-PadRST1)") (class "Default")
      (node (ref "U2") (pin "RST1") (pinfunction "RESET1_RST1") (pintype "bidirectional"))
    )
    (net (code "78") (name "unconnected-(U2-RXLED{slash}SS-PadSS)") (class "Default")
      (node (ref "U2") (pin "SS") (pinfunction "RXLED/SS_SS") (pintype "bidirectional"))
    )
  )
)
